# SCH_pi-tinker-hat_2025-06-06.net
KiCad netlist of a schematic drawn in EasyEDA
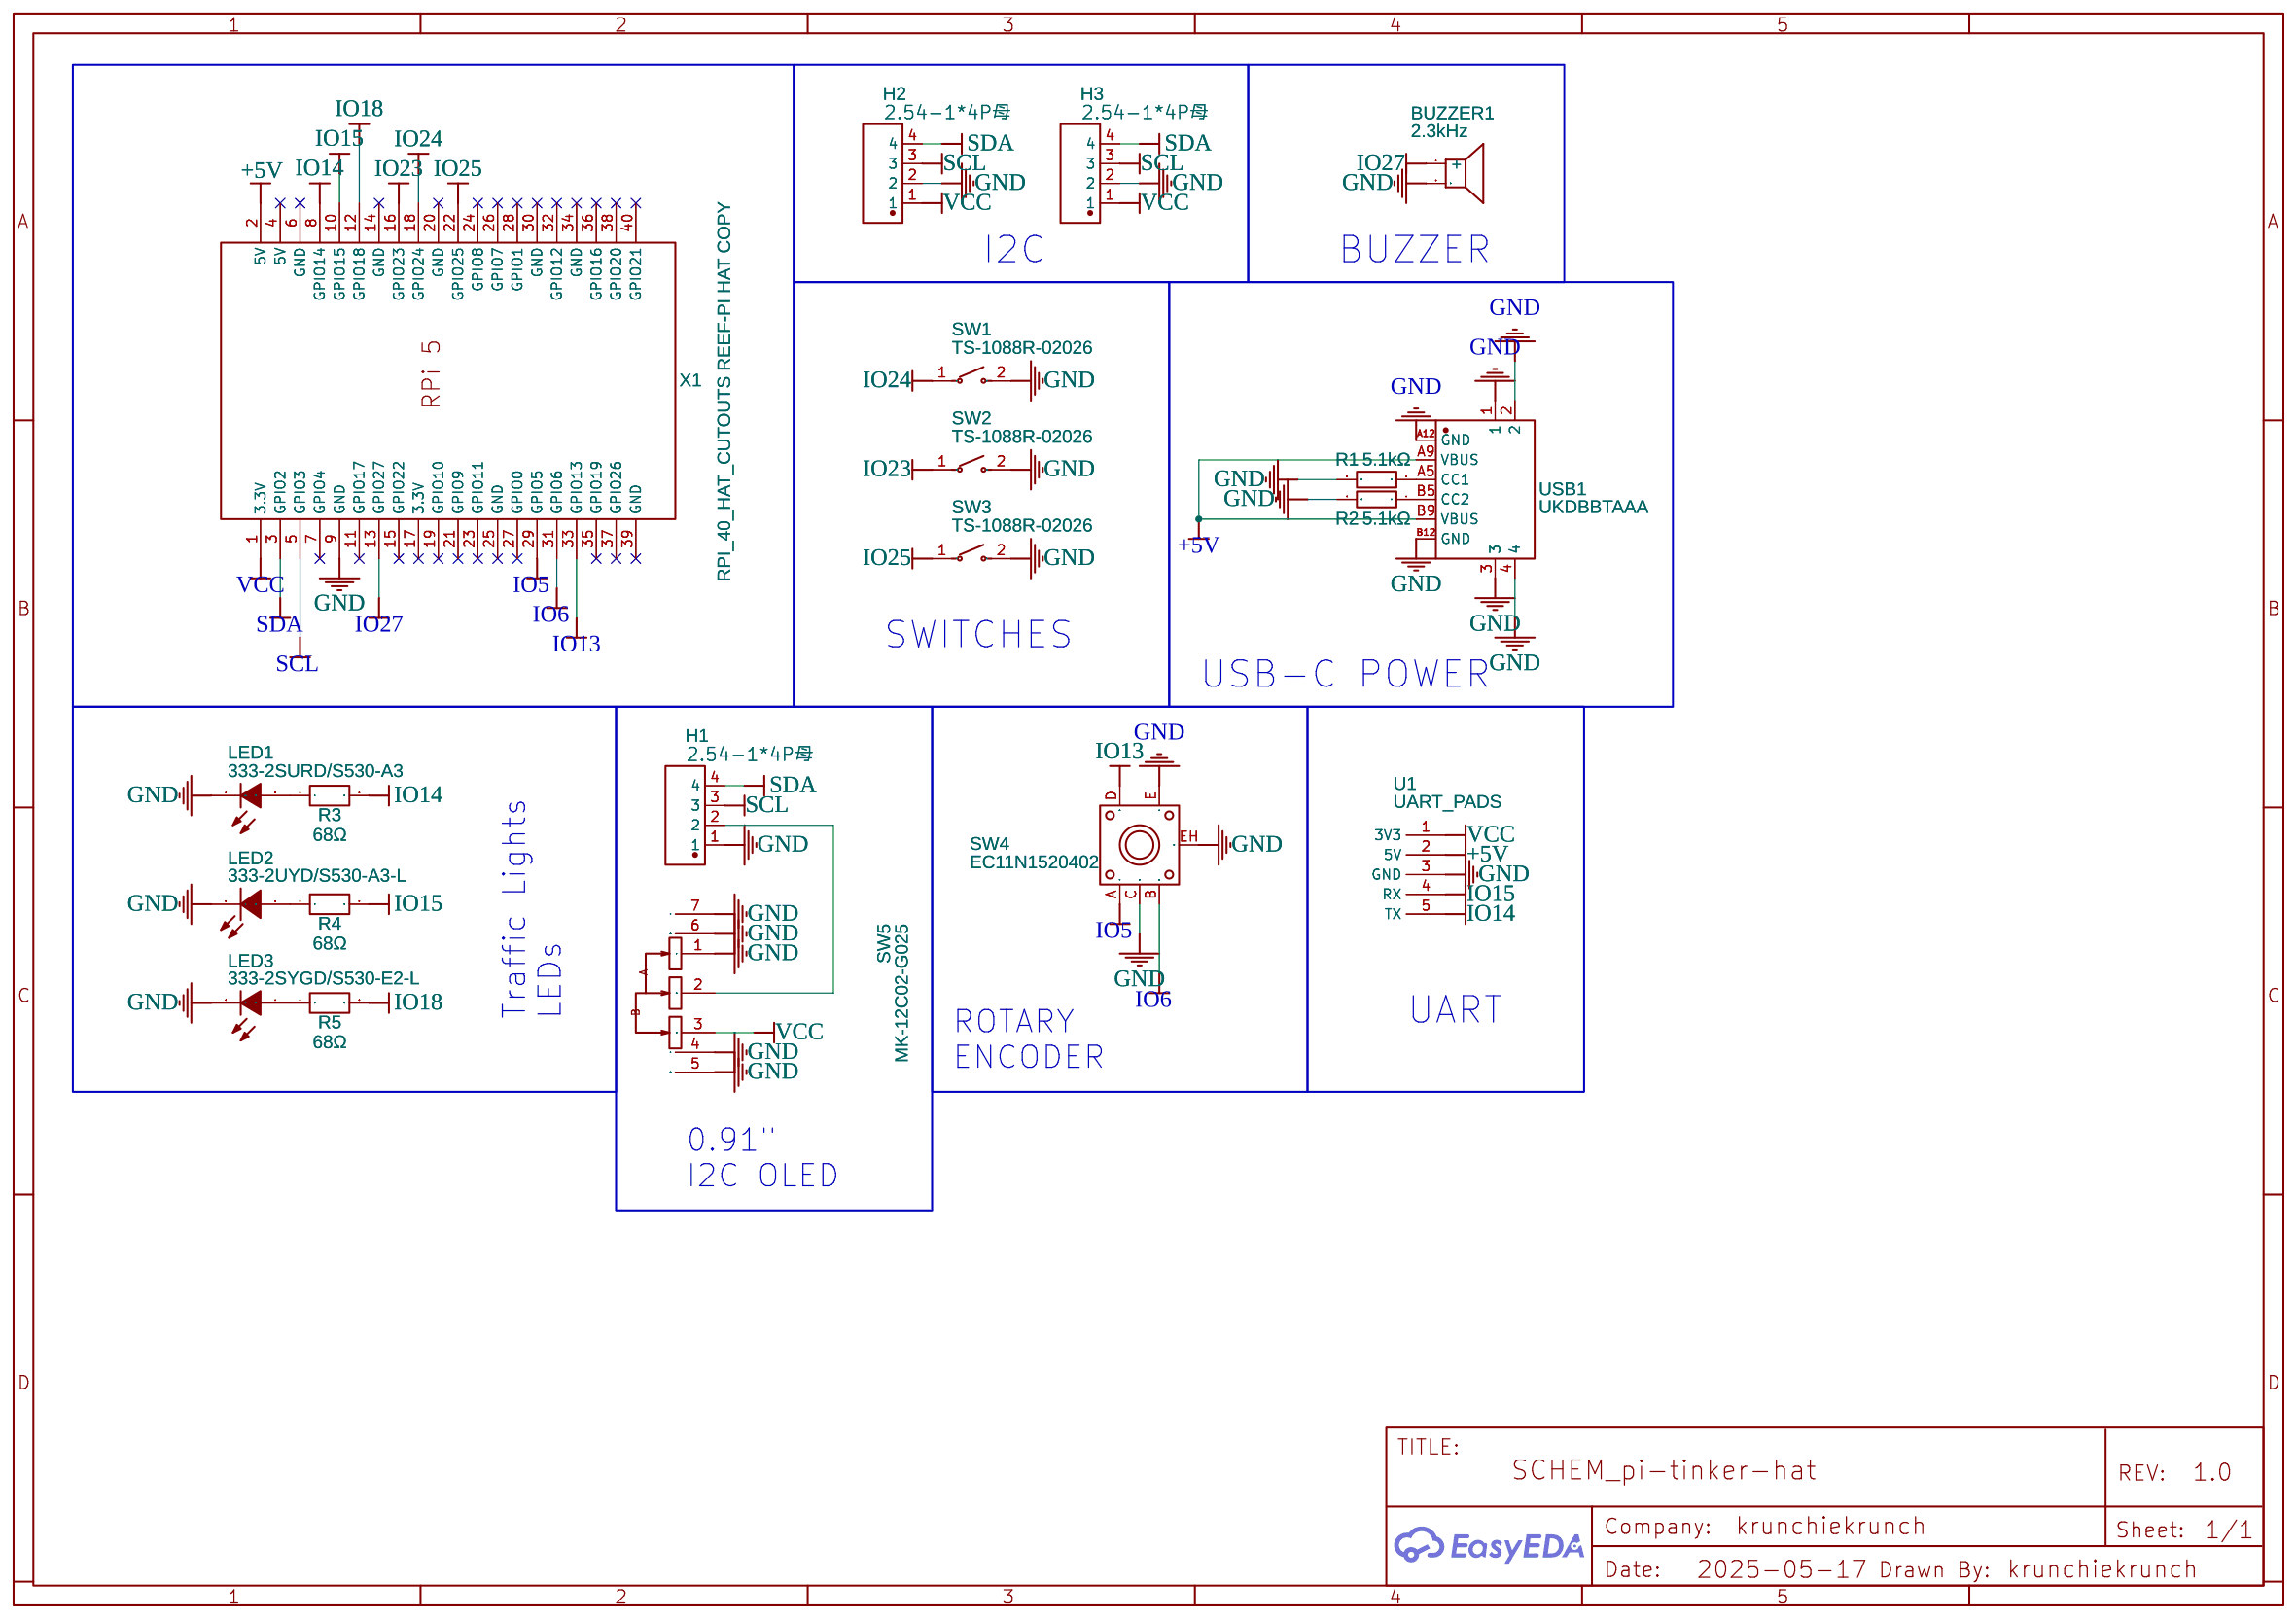
[diagram p0: schematic sheet]

(export (version "E")
  (design (tool "Eeschema 10.0.6"))
  (components
    (comp (ref "BUZZER1")
      (value "2.3kHz")
      (fields (field (name "Manufacturer Part") "TMB12A05") (field (name "Manufacturer") "华能"))
      (libsource (lib "") (part "TMB12A05"))
    )
    (comp (ref "H1")
      (value "2.54-1*4P母")
      (fields (field (name "Manufacturer") "BOOMELE(博穆精密)"))
      (libsource (lib "") (part "2.54-1*4P母"))
    )
    (comp (ref "H2")
      (value "2.54-1*4P母")
      (fields (field (name "Manufacturer") "BOOMELE(博穆精密)"))
      (libsource (lib "") (part "2.54-1*4P母"))
    )
    (comp (ref "H3")
      (value "2.54-1*4P母")
      (fields (field (name "Manufacturer") "BOOMELE(博穆精密)"))
      (libsource (lib "") (part "2.54-1*4P母"))
    )
    (comp (ref "LED1")
      (value "333-2SURD/S530-A3")
      (fields (field (name "Manufacturer") "EVERLIGHT(亿光)"))
      (libsource (lib "") (part "333-2SURD/S530-A3"))
    )
    (comp (ref "LED2")
      (value "333-2UYD/S530-A3-L")
      (fields (field (name "Manufacturer") "EVERLIGHT(亿光)"))
      (libsource (lib "") (part "333-2UYD/S530-A3-L"))
    )
    (comp (ref "LED3")
      (value "333-2SYGD/S530-E2-L")
      (fields (field (name "Manufacturer") "EVERLIGHT(亿光)"))
      (libsource (lib "") (part "333-2SYGD/S530-E2-L"))
    )
    (comp (ref "R1")
      (value "5.1kΩ")
      (fields (field (name "Manufacturer Part") "AECR0805F5K10K9") (field (name "Manufacturer") "RESI(开步睿思)"))
      (libsource (lib "") (part "AECR0805F5K10K9"))
    )
    (comp (ref "R2")
      (value "5.1kΩ")
      (fields (field (name "Manufacturer Part") "AECR0805F5K10K9") (field (name "Manufacturer") "RESI(开步睿思)"))
      (libsource (lib "") (part "AECR0805F5K10K9"))
    )
    (comp (ref "R3")
      (value "68Ω")
      (fields (field (name "Manufacturer Part") "FRC0805J680 TS") (field (name "Manufacturer") "FOJAN(富捷)"))
      (libsource (lib "") (part "FRC0805J680 TS"))
    )
    (comp (ref "R4")
      (value "68Ω")
      (fields (field (name "Manufacturer Part") "FRC0805J680 TS") (field (name "Manufacturer") "FOJAN(富捷)"))
      (libsource (lib "") (part "FRC0805J680 TS"))
    )
    (comp (ref "R5")
      (value "68Ω")
      (fields (field (name "Manufacturer Part") "FRC0805J680 TS") (field (name "Manufacturer") "FOJAN(富捷)"))
      (libsource (lib "") (part "FRC0805J680 TS"))
    )
    (comp (ref "SW1")
      (value "TS-1088R-02026")
      (fields (field (name "Manufacturer") "XUNPU(讯普)"))
      (libsource (lib "") (part "TS-1088R-02026"))
    )
    (comp (ref "SW2")
      (value "TS-1088R-02026")
      (fields (field (name "Manufacturer") "XUNPU(讯普)"))
      (libsource (lib "") (part "TS-1088R-02026"))
    )
    (comp (ref "SW3")
      (value "TS-1088R-02026")
      (fields (field (name "Manufacturer") "XUNPU(讯普)"))
      (libsource (lib "") (part "TS-1088R-02026"))
    )
    (comp (ref "SW4")
      (value "EC11N1520402")
      (fields (field (name "Manufacturer") "ALPSALPINE(阿尔卑斯阿尔派)"))
      (libsource (lib "") (part "EC11N1520402"))
    )
    (comp (ref "SW5")
      (value "MK-12C02-G025")
      (fields (field (name "Manufacturer") "G-Switch(品赞)"))
      (libsource (lib "") (part "MK-12C02-G025"))
    )
    (comp (ref "U1") (value "UART_PADS") (libsource (lib "") (part "UART_PADS")))
    (comp (ref "USB1")
      (value "UKDBBTAAA")
      (fields (field (name "Manufacturer") "SAMZO(三佐)"))
      (libsource (lib "") (part "UKDBBTAAA"))
    )
    (comp (ref "X1")
      (value "RPI_40_HAT_CUTOUTS REEF-PI HAT COPY")
      (fields (field (name "Manufacturer") "Raspberry Pi 5 4GB"))
      (libsource (lib "") (part "Raspberry Pi 5"))
    )
  )
  (nets
    (net (code "1") (name "+5V") (class "Default")
      (node (ref "U1") (pin "2") (pinfunction "5V_2") (pintype "unspecified"))
      (node (ref "USB1") (pin "A9") (pinfunction "VBUS_A9") (pintype "unspecified"))
      (node (ref "USB1") (pin "B9") (pinfunction "VBUS_B9") (pintype "unspecified"))
      (node (ref "X1") (pin "2") (pinfunction "5V_2") (pintype "passive"))
    )
    (net (code "2") (name "GND") (class "Default")
      (node (ref "BUZZER1") (pin "2") (pinfunction "2_2") (pintype "unspecified"))
      (node (ref "H1") (pin "1") (pinfunction "1_1") (pintype "unspecified"))
      (node (ref "H2") (pin "2") (pinfunction "2_2") (pintype "unspecified"))
      (node (ref "H3") (pin "2") (pinfunction "2_2") (pintype "unspecified"))
      (node (ref "LED1") (pin "1") (pinfunction "C_1") (pintype "input"))
      (node (ref "LED2") (pin "2") (pinfunction "K_2") (pintype "unspecified"))
      (node (ref "LED3") (pin "2") (pinfunction "K_2") (pintype "input"))
      (node (ref "R1") (pin "2") (pinfunction "2_2") (pintype "unspecified"))
      (node (ref "R2") (pin "2") (pinfunction "2_2") (pintype "unspecified"))
      (node (ref "SW1") (pin "2") (pinfunction "2_2") (pintype "unspecified"))
      (node (ref "SW2") (pin "2") (pinfunction "2_2") (pintype "unspecified"))
      (node (ref "SW3") (pin "2") (pinfunction "2_2") (pintype "unspecified"))
      (node (ref "SW4") (pin "C") (pinfunction "C_C") (pintype "unspecified"))
      (node (ref "SW4") (pin "E") (pinfunction "E_E") (pintype "unspecified"))
      (node (ref "SW4") (pin "EH") (pinfunction "EH_EH") (pintype "unspecified"))
      (node (ref "SW5") (pin "1") (pinfunction "1_1") (pintype "unspecified"))
      (node (ref "SW5") (pin "4") (pinfunction "4_4") (pintype "unspecified"))
      (node (ref "SW5") (pin "5") (pinfunction "5_5") (pintype "unspecified"))
      (node (ref "SW5") (pin "6") (pinfunction "6_6") (pintype "unspecified"))
      (node (ref "SW5") (pin "7") (pinfunction "7_7") (pintype "unspecified"))
      (node (ref "U1") (pin "3") (pinfunction "GND_3") (pintype "unspecified"))
      (node (ref "USB1") (pin "1") (pinfunction "1_1") (pintype "unspecified"))
      (node (ref "USB1") (pin "2") (pinfunction "2_2") (pintype "unspecified"))
      (node (ref "USB1") (pin "3") (pinfunction "3_3") (pintype "unspecified"))
      (node (ref "USB1") (pin "4") (pinfunction "4_4") (pintype "unspecified"))
      (node (ref "USB1") (pin "A12") (pinfunction "GND_A12") (pintype "unspecified"))
      (node (ref "USB1") (pin "B12") (pinfunction "GND_B12") (pintype "unspecified"))
      (node (ref "X1") (pin "9") (pinfunction "GND_9") (pintype "unspecified"))
    )
    (net (code "3") (name "IO5") (class "Default")
      (node (ref "SW4") (pin "A") (pinfunction "A_A") (pintype "unspecified"))
      (node (ref "X1") (pin "29") (pinfunction "GPIO5_29") (pintype "bidirectional"))
    )
    (net (code "4") (name "IO6") (class "Default")
      (node (ref "SW4") (pin "B") (pinfunction "B_B") (pintype "unspecified"))
      (node (ref "X1") (pin "31") (pinfunction "GPIO6_31") (pintype "bidirectional"))
    )
    (net (code "5") (name "IO13") (class "Default")
      (node (ref "SW4") (pin "D") (pinfunction "D_D") (pintype "unspecified"))
      (node (ref "X1") (pin "33") (pinfunction "GPIO13_33") (pintype "bidirectional"))
    )
    (net (code "6") (name "IO14") (class "Default")
      (node (ref "R3") (pin "2") (pinfunction "2_2") (pintype "unspecified"))
      (node (ref "U1") (pin "5") (pinfunction "TX_5") (pintype "unspecified"))
      (node (ref "X1") (pin "8") (pinfunction "GPIO14_8") (pintype "bidirectional"))
    )
    (net (code "7") (name "IO15") (class "Default")
      (node (ref "R4") (pin "2") (pinfunction "2_2") (pintype "unspecified"))
      (node (ref "U1") (pin "4") (pinfunction "RX_4") (pintype "unspecified"))
      (node (ref "X1") (pin "10") (pinfunction "GPIO15_10") (pintype "bidirectional"))
    )
    (net (code "8") (name "IO18") (class "Default")
      (node (ref "R5") (pin "2") (pinfunction "2_2") (pintype "unspecified"))
      (node (ref "X1") (pin "12") (pinfunction "GPIO18_12") (pintype "bidirectional"))
    )
    (net (code "9") (name "IO23") (class "Default")
      (node (ref "SW2") (pin "1") (pinfunction "1_1") (pintype "unspecified"))
      (node (ref "X1") (pin "16") (pinfunction "GPIO23_16") (pintype "bidirectional"))
    )
    (net (code "10") (name "IO24") (class "Default")
      (node (ref "SW1") (pin "1") (pinfunction "1_1") (pintype "unspecified"))
      (node (ref "X1") (pin "18") (pinfunction "GPIO24_18") (pintype "bidirectional"))
    )
    (net (code "11") (name "IO25") (class "Default")
      (node (ref "SW3") (pin "1") (pinfunction "1_1") (pintype "unspecified"))
      (node (ref "X1") (pin "22") (pinfunction "GPIO25_22") (pintype "bidirectional"))
    )
    (net (code "12") (name "IO27") (class "Default")
      (node (ref "BUZZER1") (pin "1") (pinfunction "+_1") (pintype "unspecified"))
      (node (ref "X1") (pin "13") (pinfunction "GPIO27_13") (pintype "bidirectional"))
    )
    (net (code "13") (name "Net-(H1-Pad2)") (class "Default")
      (node (ref "H1") (pin "2") (pinfunction "2_2") (pintype "unspecified"))
      (node (ref "SW5") (pin "2") (pinfunction "2_2") (pintype "unspecified"))
    )
    (net (code "14") (name "Net-(LED1-A)") (class "Default")
      (node (ref "LED1") (pin "2") (pinfunction "A_2") (pintype "input"))
      (node (ref "R3") (pin "1") (pinfunction "1_1") (pintype "unspecified"))
    )
    (net (code "15") (name "Net-(LED2-A)") (class "Default")
      (node (ref "LED2") (pin "1") (pinfunction "A_1") (pintype "unspecified"))
      (node (ref "R4") (pin "1") (pinfunction "1_1") (pintype "unspecified"))
    )
    (net (code "16") (name "Net-(LED3-A)") (class "Default")
      (node (ref "LED3") (pin "1") (pinfunction "A_1") (pintype "input"))
      (node (ref "R5") (pin "1") (pinfunction "1_1") (pintype "unspecified"))
    )
    (net (code "17") (name "Net-(USB1-CC1)") (class "Default")
      (node (ref "R1") (pin "1") (pinfunction "1_1") (pintype "unspecified"))
      (node (ref "USB1") (pin "A5") (pinfunction "CC1_A5") (pintype "unspecified"))
    )
    (net (code "18") (name "Net-(USB1-CC2)") (class "Default")
      (node (ref "R2") (pin "1") (pinfunction "1_1") (pintype "unspecified"))
      (node (ref "USB1") (pin "B5") (pinfunction "CC2_B5") (pintype "unspecified"))
    )
    (net (code "19") (name "SCL") (class "Default")
      (node (ref "H1") (pin "3") (pinfunction "3_3") (pintype "unspecified"))
      (node (ref "H2") (pin "3") (pinfunction "3_3") (pintype "unspecified"))
      (node (ref "H3") (pin "3") (pinfunction "3_3") (pintype "unspecified"))
      (node (ref "X1") (pin "5") (pinfunction "GPIO3_5") (pintype "bidirectional"))
    )
    (net (code "20") (name "SDA") (class "Default")
      (node (ref "H1") (pin "4") (pinfunction "4_4") (pintype "unspecified"))
      (node (ref "H2") (pin "4") (pinfunction "4_4") (pintype "unspecified"))
      (node (ref "H3") (pin "4") (pinfunction "4_4") (pintype "unspecified"))
      (node (ref "X1") (pin "3") (pinfunction "GPIO2_3") (pintype "bidirectional"))
    )
    (net (code "21") (name "VCC") (class "Default")
      (node (ref "H2") (pin "1") (pinfunction "1_1") (pintype "unspecified"))
      (node (ref "H3") (pin "1") (pinfunction "1_1") (pintype "unspecified"))
      (node (ref "SW5") (pin "3") (pinfunction "3_3") (pintype "unspecified"))
      (node (ref "U1") (pin "1") (pinfunction "3V3_1") (pintype "unspecified"))
      (node (ref "X1") (pin "1") (pinfunction "3.3V_1") (pintype "passive"))
    )
    (net (code "22") (name "unconnected-(X1-3.3V-Pad17)") (class "Default")
      (node (ref "X1") (pin "17") (pinfunction "3.3V_17") (pintype "passive+no_connect"))
    )
    (net (code "23") (name "unconnected-(X1-5V-Pad4)") (class "Default")
      (node (ref "X1") (pin "4") (pinfunction "5V_4") (pintype "passive+no_connect"))
    )
    (net (code "24") (name "unconnected-(X1-GND-Pad6)") (class "Default")
      (node (ref "X1") (pin "6") (pinfunction "GND_6") (pintype "unspecified+no_connect"))
    )
    (net (code "25") (name "unconnected-(X1-GND-Pad14)") (class "Default")
      (node (ref "X1") (pin "14") (pinfunction "GND_14") (pintype "unspecified+no_connect"))
    )
    (net (code "26") (name "unconnected-(X1-GND-Pad20)") (class "Default")
      (node (ref "X1") (pin "20") (pinfunction "GND_20") (pintype "unspecified+no_connect"))
    )
    (net (code "27") (name "unconnected-(X1-GND-Pad25)") (class "Default")
      (node (ref "X1") (pin "25") (pinfunction "GND_25") (pintype "unspecified+no_connect"))
    )
    (net (code "28") (name "unconnected-(X1-GND-Pad30)") (class "Default")
      (node (ref "X1") (pin "30") (pinfunction "GND_30") (pintype "unspecified+no_connect"))
    )
    (net (code "29") (name "unconnected-(X1-GND-Pad34)") (class "Default")
      (node (ref "X1") (pin "34") (pinfunction "GND_34") (pintype "unspecified+no_connect"))
    )
    (net (code "30") (name "unconnected-(X1-GND-Pad39)") (class "Default")
      (node (ref "X1") (pin "39") (pinfunction "GND_39") (pintype "unspecified+no_connect"))
    )
    (net (code "31") (name "unconnected-(X1-GPIO0-Pad27)") (class "Default")
      (node (ref "X1") (pin "27") (pinfunction "GPIO0_27") (pintype "unspecified+no_connect"))
    )
    (net (code "32") (name "unconnected-(X1-GPIO1-Pad28)") (class "Default")
      (node (ref "X1") (pin "28") (pinfunction "GPIO1_28") (pintype "unspecified+no_connect"))
    )
    (net (code "33") (name "unconnected-(X1-GPIO4-Pad7)") (class "Default")
      (node (ref "X1") (pin "7") (pinfunction "GPIO4_7") (pintype "bidirectional+no_connect"))
    )
    (net (code "34") (name "unconnected-(X1-GPIO7-Pad26)") (class "Default")
      (node (ref "X1") (pin "26") (pinfunction "GPIO7_26") (pintype "bidirectional+no_connect"))
    )
    (net (code "35") (name "unconnected-(X1-GPIO8-Pad24)") (class "Default")
      (node (ref "X1") (pin "24") (pinfunction "GPIO8_24") (pintype "bidirectional+no_connect"))
    )
    (net (code "36") (name "unconnected-(X1-GPIO9-Pad21)") (class "Default")
      (node (ref "X1") (pin "21") (pinfunction "GPIO9_21") (pintype "bidirectional+no_connect"))
    )
    (net (code "37") (name "unconnected-(X1-GPIO10-Pad19)") (class "Default")
      (node (ref "X1") (pin "19") (pinfunction "GPIO10_19") (pintype "bidirectional+no_connect"))
    )
    (net (code "38") (name "unconnected-(X1-GPIO11-Pad23)") (class "Default")
      (node (ref "X1") (pin "23") (pinfunction "GPIO11_23") (pintype "bidirectional+no_connect"))
    )
    (net (code "39") (name "unconnected-(X1-GPIO12-Pad32)") (class "Default")
      (node (ref "X1") (pin "32") (pinfunction "GPIO12_32") (pintype "bidirectional+no_connect"))
    )
    (net (code "40") (name "unconnected-(X1-GPIO16-Pad36)") (class "Default")
      (node (ref "X1") (pin "36") (pinfunction "GPIO16_36") (pintype "bidirectional+no_connect"))
    )
    (net (code "41") (name "unconnected-(X1-GPIO17-Pad11)") (class "Default")
      (node (ref "X1") (pin "11") (pinfunction "GPIO17_11") (pintype "bidirectional+no_connect"))
    )
    (net (code "42") (name "unconnected-(X1-GPIO19-Pad35)") (class "Default")
      (node (ref "X1") (pin "35") (pinfunction "GPIO19_35") (pintype "bidirectional+no_connect"))
    )
    (net (code "43") (name "unconnected-(X1-GPIO20-Pad38)") (class "Default")
      (node (ref "X1") (pin "38") (pinfunction "GPIO20_38") (pintype "bidirectional+no_connect"))
    )
    (net (code "44") (name "unconnected-(X1-GPIO21-Pad40)") (class "Default")
      (node (ref "X1") (pin "40") (pinfunction "GPIO21_40") (pintype "bidirectional+no_connect"))
    )
    (net (code "45") (name "unconnected-(X1-GPIO22-Pad15)") (class "Default")
      (node (ref "X1") (pin "15") (pinfunction "GPIO22_15") (pintype "bidirectional+no_connect"))
    )
    (net (code "46") (name "unconnected-(X1-GPIO26-Pad37)") (class "Default")
      (node (ref "X1") (pin "37") (pinfunction "GPIO26_37") (pintype "bidirectional+no_connect"))
    )
  )
)
